# misc.net
KiCad netlist of a schematic drawn in Altium Designer
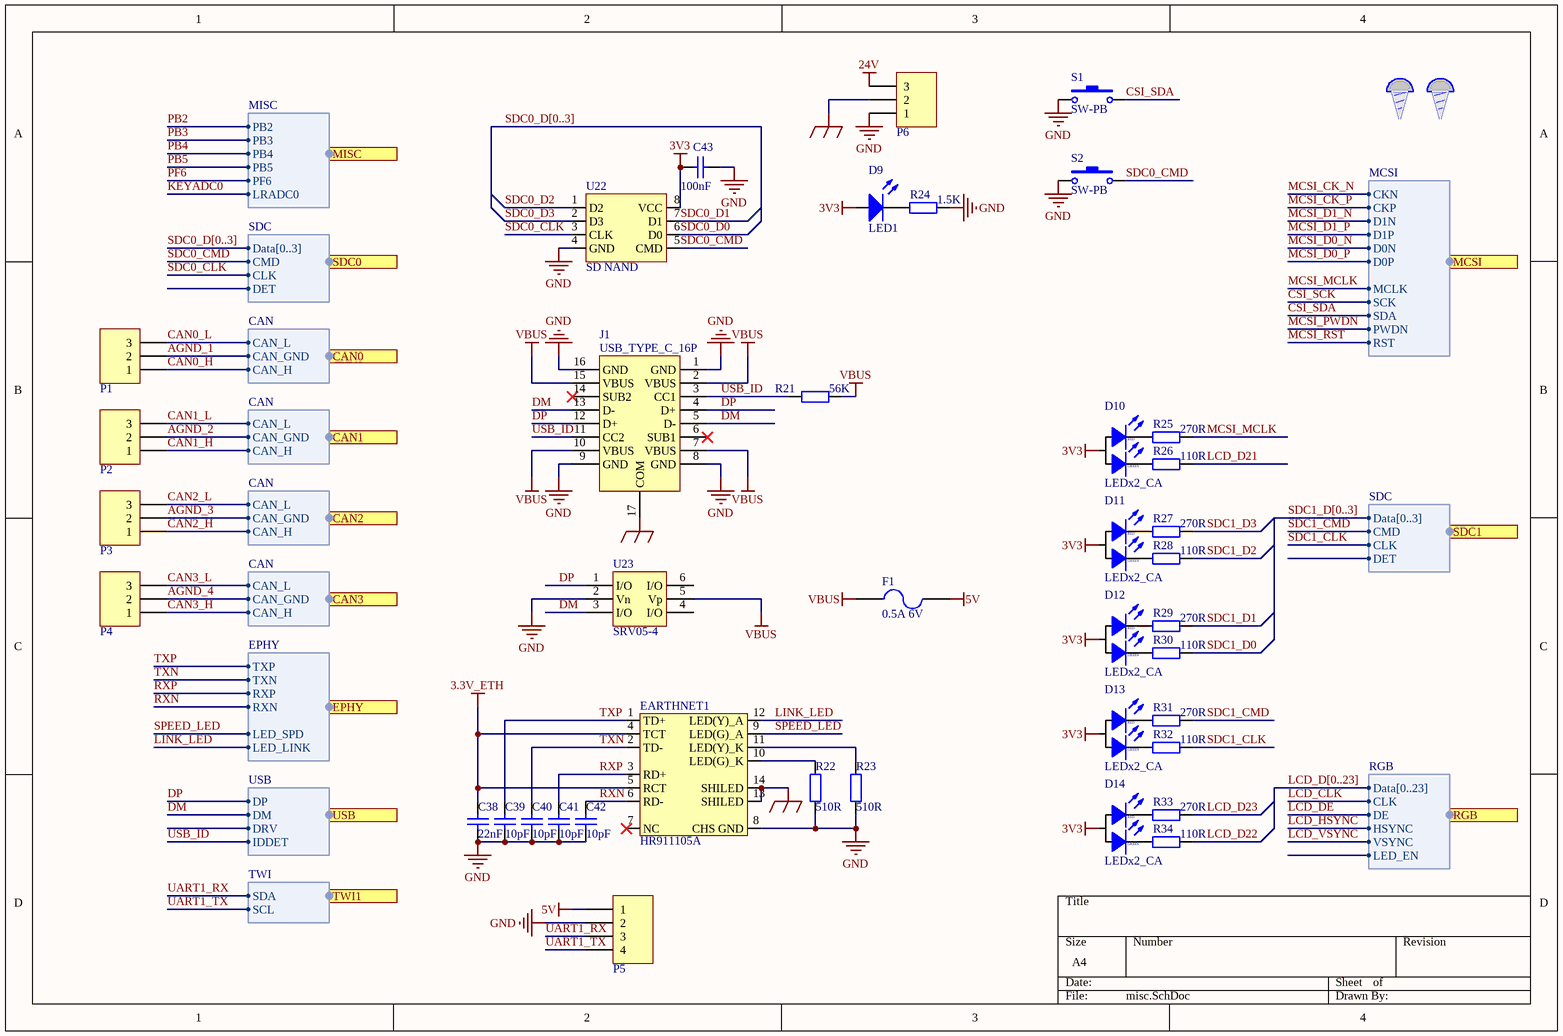
[diagram p0: misc.SchDoc]

(export (version "E")
  (design (tool "Eeschema 10.0.6"))
  (components
    (comp (ref "C38")
      (value "22nF")
      (footprint "CAPC1608L")
      (description "Capacitor")
      (fields (field (name "PUBLISHER") "Altium Limited"))
      (libsource (lib "Peace的集成库") (part "Cap1"))
    )
    (comp (ref "C39")
      (value "10pF")
      (footprint "CAPC1608L")
      (description "Capacitor")
      (fields (field (name "PUBLISHER") "Altium Limited"))
      (libsource (lib "Peace的集成库") (part "Cap1"))
    )
    (comp (ref "C40")
      (value "10pF")
      (footprint "CAPC1608L")
      (description "Capacitor")
      (fields (field (name "PUBLISHER") "Altium Limited"))
      (libsource (lib "Peace的集成库") (part "Cap1"))
    )
    (comp (ref "C41")
      (value "10pF")
      (footprint "CAPC1608L")
      (description "Capacitor")
      (fields (field (name "PUBLISHER") "Altium Limited"))
      (libsource (lib "Peace的集成库") (part "Cap1"))
    )
    (comp (ref "C42")
      (value "10pF")
      (footprint "CAPC1608L")
      (description "Capacitor")
      (fields (field (name "PUBLISHER") "Altium Limited"))
      (libsource (lib "Peace的集成库") (part "Cap1"))
    )
    (comp (ref "C43")
      (value "100nF")
      (footprint "CAPC1608L")
      (description "Capacitor")
      (fields (field (name "PUBLISHER") "Altium Limited"))
      (libsource (lib "Peace的集成库") (part "Cap1"))
    )
    (comp (ref "D9")
      (value "LED1")
      (footprint "LED_3")
      (description "Typical RED GaAs LED")
      (fields (field (name "PUBLISHER") "Altium Limited"))
      (libsource (lib "Peace的集成库") (part "LED1"))
    )
    (comp (ref "D10")
      (value "LEDx2_CA")
      (footprint "LED_3x2")
      (description "共阳红绿双色二极管")
      (fields (field (name "PUBLISHER") "Altium Limited"))
      (libsource (lib "Peace的集成库") (part "LEDx2_CA"))
    )
    (comp (ref "D11")
      (value "LEDx2_CA")
      (footprint "LED_3x2")
      (description "共阳红绿双色二极管")
      (fields (field (name "PUBLISHER") "Altium Limited"))
      (libsource (lib "Peace的集成库") (part "LEDx2_CA"))
    )
    (comp (ref "D12")
      (value "LEDx2_CA")
      (footprint "LED_3x2")
      (description "共阳红绿双色二极管")
      (fields (field (name "PUBLISHER") "Altium Limited"))
      (libsource (lib "Peace的集成库") (part "LEDx2_CA"))
    )
    (comp (ref "D13")
      (value "LEDx2_CA")
      (footprint "LED_3x2")
      (description "共阳红绿双色二极管")
      (fields (field (name "PUBLISHER") "Altium Limited"))
      (libsource (lib "Peace的集成库") (part "LEDx2_CA"))
    )
    (comp (ref "D14")
      (value "LEDx2_CA")
      (footprint "LED_3x2")
      (description "共阳红绿双色二极管")
      (fields (field (name "PUBLISHER") "Altium Limited"))
      (libsource (lib "Peace的集成库") (part "LEDx2_CA"))
    )
    (comp (ref "EARTHNET1")
      (value "HR911105A")
      (footprint "HR911105A")
      (libsource (lib "原理图库") (part "HR911105A"))
    )
    (comp (ref "F1")
      (value "0.5A 6V")
      (footprint "FUSE2012L")
      (description "Fuse")
      (fields (field (name "PUBLISHER") "Altium Limited"))
      (libsource (lib "Peace的集成库") (part "Fuse 2"))
    )
    (comp (ref "J1")
      (value "USB_TYPE_C_16P")
      (footprint "USB_TYPEC_16P")
      (libsource (lib "Peace的集成库") (part "USB_TYPE_C_16P"))
    )
    (comp (ref "M1") (value "M") (footprint "M3") (libsource (lib "Peace的集成库") (part "M")))
    (comp (ref "M2") (value "M") (footprint "M3") (libsource (lib "Peace的集成库") (part "M")))
    (comp (ref "P1")
      (value "Header 3")
      (footprint "KF2EDGR-5.08-3P_S")
      (description "Header, 3-Pin")
      (fields (field (name "PUBLISHER") "Altium Limited"))
      (libsource (lib "Peace的集成库") (part "Header 3"))
    )
    (comp (ref "P2")
      (value "Header 3")
      (footprint "KF2EDGR-5.08-3P_S")
      (description "Header, 3-Pin")
      (fields (field (name "PUBLISHER") "Altium Limited"))
      (libsource (lib "Peace的集成库") (part "Header 3"))
    )
    (comp (ref "P3")
      (value "Header 3")
      (footprint "KF2EDGR-5.08-3P_S")
      (description "Header, 3-Pin")
      (fields (field (name "PUBLISHER") "Altium Limited"))
      (libsource (lib "Peace的集成库") (part "Header 3"))
    )
    (comp (ref "P4")
      (value "Header 3")
      (footprint "KF2EDGR-5.08-3P_S")
      (description "Header, 3-Pin")
      (fields (field (name "PUBLISHER") "Altium Limited"))
      (libsource (lib "Peace的集成库") (part "Header 3"))
    )
    (comp (ref "P5")
      (value "Header 4")
      (footprint "HDR1X4")
      (description "Header, 4-Pin")
      (fields (field (name "PUBLISHER") "Altium Limited"))
      (libsource (lib "Peace的集成库") (part "Header 4"))
    )
    (comp (ref "P6")
      (value "Header 3")
      (footprint "KF2EDGR-5.08-3P_S")
      (description "Header, 3-Pin")
      (fields (field (name "PUBLISHER") "Altium Limited"))
      (libsource (lib "") (part "Header 3_1"))
    )
    (comp (ref "R21")
      (value "56K")
      (footprint "RESC1005L")
      (description "Resistor")
      (fields (field (name "PUBLISHER") "Altium Limited"))
      (libsource (lib "Peace的集成库") (part "Res1"))
    )
    (comp (ref "R22")
      (value "510R")
      (footprint "RESC1608L")
      (description "Resistor")
      (fields (field (name "PUBLISHER") "Altium Limited"))
      (libsource (lib "") (part "Res1_1"))
    )
    (comp (ref "R23")
      (value "510R")
      (footprint "RESC1608L")
      (description "Resistor")
      (fields (field (name "PUBLISHER") "Altium Limited"))
      (libsource (lib "") (part "Res1_1"))
    )
    (comp (ref "R24")
      (value "1.5K")
      (footprint "RESC1608L")
      (description "Resistor")
      (fields (field (name "PUBLISHER") "Altium Limited"))
      (libsource (lib "Peace的集成库") (part "Res1"))
    )
    (comp (ref "R25")
      (value "270R")
      (footprint "RESC1608L")
      (description "Resistor")
      (fields (field (name "PUBLISHER") "Altium Limited"))
      (libsource (lib "Peace的集成库") (part "Res1"))
    )
    (comp (ref "R26")
      (value "110R")
      (footprint "RESC1608L")
      (description "Resistor")
      (fields (field (name "PUBLISHER") "Altium Limited"))
      (libsource (lib "Peace的集成库") (part "Res1"))
    )
    (comp (ref "R27")
      (value "270R")
      (footprint "RESC1608L")
      (description "Resistor")
      (fields (field (name "PUBLISHER") "Altium Limited"))
      (libsource (lib "Peace的集成库") (part "Res1"))
    )
    (comp (ref "R28")
      (value "110R")
      (footprint "RESC1608L")
      (description "Resistor")
      (fields (field (name "PUBLISHER") "Altium Limited"))
      (libsource (lib "Peace的集成库") (part "Res1"))
    )
    (comp (ref "R29")
      (value "270R")
      (footprint "RESC1608L")
      (description "Resistor")
      (fields (field (name "PUBLISHER") "Altium Limited"))
      (libsource (lib "Peace的集成库") (part "Res1"))
    )
    (comp (ref "R30")
      (value "110R")
      (footprint "RESC1608L")
      (description "Resistor")
      (fields (field (name "PUBLISHER") "Altium Limited"))
      (libsource (lib "Peace的集成库") (part "Res1"))
    )
    (comp (ref "R31")
      (value "270R")
      (footprint "RESC1608L")
      (description "Resistor")
      (fields (field (name "PUBLISHER") "Altium Limited"))
      (libsource (lib "Peace的集成库") (part "Res1"))
    )
    (comp (ref "R32")
      (value "110R")
      (footprint "RESC1608L")
      (description "Resistor")
      (fields (field (name "PUBLISHER") "Altium Limited"))
      (libsource (lib "Peace的集成库") (part "Res1"))
    )
    (comp (ref "R33")
      (value "270R")
      (footprint "RESC1608L")
      (description "Resistor")
      (fields (field (name "PUBLISHER") "Altium Limited"))
      (libsource (lib "Peace的集成库") (part "Res1"))
    )
    (comp (ref "R34")
      (value "110R")
      (footprint "RESC1608L")
      (description "Resistor")
      (fields (field (name "PUBLISHER") "Altium Limited"))
      (libsource (lib "Peace的集成库") (part "Res1"))
    )
    (comp (ref "S1")
      (value "SW-PB")
      (footprint "SW_4.5x3.8")
      (description "Switch")
      (fields (field (name "PUBLISHER") "Altium Limited"))
      (libsource (lib "Peace的集成库") (part "SW-PB"))
    )
    (comp (ref "S2")
      (value "SW-PB")
      (footprint "SW-3x6")
      (description "Switch")
      (fields (field (name "PUBLISHER") "Altium Limited"))
      (libsource (lib "Peace的集成库") (part "SW-PB"))
    )
    (comp (ref "U22")
      (value "SD NAND")
      (footprint "QFN8_L")
      (description "贴片式SD卡")
      (libsource (lib "Peace的集成库") (part "SD NAND"))
    )
    (comp (ref "U23")
      (value "SRV05-4")
      (footprint "SOT23-6_L")
      (libsource (lib "Peace的集成库") (part "NUP4201"))
    )
  )
  (nets
    (net (code "10") (name "/AGND_1") (class "Default")
      (node (ref "P1") (pin "2") (pinfunction "2_2") (pintype "passive"))
    )
    (net (code "11") (name "/AGND_2") (class "Default")
      (node (ref "P2") (pin "2") (pinfunction "2_2") (pintype "passive"))
    )
    (net (code "12") (name "/AGND_3") (class "Default")
      (node (ref "P3") (pin "2") (pinfunction "2_2") (pintype "passive"))
    )
    (net (code "13") (name "/AGND_4") (class "Default")
      (node (ref "P4") (pin "2") (pinfunction "2_2") (pintype "passive"))
    )
    (net (code "14") (name "/CAN0_H") (class "Default")
      (node (ref "P1") (pin "1") (pinfunction "1_1") (pintype "passive"))
    )
    (net (code "15") (name "/CAN0_L") (class "Default")
      (node (ref "P1") (pin "3") (pinfunction "3_3") (pintype "passive"))
    )
    (net (code "16") (name "/CAN1_H") (class "Default")
      (node (ref "P2") (pin "1") (pinfunction "1_1") (pintype "passive"))
    )
    (net (code "17") (name "/CAN1_L") (class "Default")
      (node (ref "P2") (pin "3") (pinfunction "3_3") (pintype "passive"))
    )
    (net (code "18") (name "/CAN2_H") (class "Default")
      (node (ref "P3") (pin "1") (pinfunction "1_1") (pintype "passive"))
    )
    (net (code "19") (name "/CAN2_L") (class "Default")
      (node (ref "P3") (pin "3") (pinfunction "3_3") (pintype "passive"))
    )
    (net (code "20") (name "/CAN3_H") (class "Default")
      (node (ref "P4") (pin "1") (pinfunction "1_1") (pintype "passive"))
    )
    (net (code "21") (name "/CAN3_L") (class "Default")
      (node (ref "P4") (pin "3") (pinfunction "3_3") (pintype "passive"))
    )
    (net (code "23") (name "/CSI_SDA") (class "Default")
      (node (ref "S1") (pin "2") (pinfunction "2_2") (pintype "passive"))
    )
    (net (code "24") (name "/DM") (class "Default")
      (node (ref "J1") (pin "13") (pinfunction "D-_13") (pintype "passive"))
      (node (ref "J1") (pin "5") (pinfunction "D-_5") (pintype "passive"))
      (node (ref "U23") (pin "3") (pinfunction "I/O_3") (pintype "passive"))
    )
    (net (code "25") (name "/DP") (class "Default")
      (node (ref "J1") (pin "12") (pinfunction "D+_12") (pintype "passive"))
      (node (ref "J1") (pin "4") (pinfunction "D+_4") (pintype "passive"))
      (node (ref "U23") (pin "1") (pinfunction "I/O_1") (pintype "passive"))
    )
    (net (code "28") (name "/LCD_D21") (class "Default")
      (node (ref "R26") (pin "2") (pinfunction "2_2") (pintype "passive"))
    )
    (net (code "29") (name "/LCD_D22") (class "Default")
      (node (ref "R34") (pin "2") (pinfunction "2_2") (pintype "passive"))
    )
    (net (code "30") (name "/LCD_D23") (class "Default")
      (node (ref "R33") (pin "2") (pinfunction "2_2") (pintype "passive"))
    )
    (net (code "34") (name "/LINK_LED") (class "Default")
      (node (ref "EARTHNET1") (pin "12") (pinfunction "LED(Y)_A_12") (pintype "passive"))
    )
    (net (code "41") (name "/MCSI_MCLK") (class "Default")
      (node (ref "R25") (pin "2") (pinfunction "2_2") (pintype "passive"))
    )
    (net (code "50") (name "/RXN") (class "Default")
      (node (ref "C42") (pin "2") (pinfunction "2_2") (pintype "passive"))
      (node (ref "EARTHNET1") (pin "6") (pinfunction "RD-_6") (pintype "passive"))
    )
    (net (code "51") (name "/RXP") (class "Default")
      (node (ref "C41") (pin "2") (pinfunction "2_2") (pintype "passive"))
      (node (ref "EARTHNET1") (pin "3") (pinfunction "RD+_3") (pintype "passive"))
    )
    (net (code "52") (name "/SDC0_CLK") (class "Default")
      (node (ref "U22") (pin "3") (pinfunction "CLK_3") (pintype "passive"))
    )
    (net (code "53") (name "/SDC0_CMD") (class "Default")
      (node (ref "S2") (pin "2") (pinfunction "2_2") (pintype "passive"))
      (node (ref "U22") (pin "5") (pinfunction "CMD_5") (pintype "passive"))
    )
    (net (code "54") (name "/SDC0_D0") (class "Default")
      (node (ref "U22") (pin "6") (pinfunction "D0_6") (pintype "passive"))
    )
    (net (code "55") (name "/SDC0_D1") (class "Default")
      (node (ref "U22") (pin "7") (pinfunction "D1_7") (pintype "passive"))
    )
    (net (code "56") (name "/SDC0_D2") (class "Default")
      (node (ref "U22") (pin "1") (pinfunction "D2_1") (pintype "passive"))
    )
    (net (code "57") (name "/SDC0_D3") (class "Default")
      (node (ref "U22") (pin "2") (pinfunction "D3_2") (pintype "passive"))
    )
    (net (code "60") (name "/SDC1_CLK") (class "Default")
      (node (ref "R32") (pin "2") (pinfunction "2_2") (pintype "passive"))
    )
    (net (code "61") (name "/SDC1_CMD") (class "Default")
      (node (ref "R31") (pin "2") (pinfunction "2_2") (pintype "passive"))
    )
    (net (code "62") (name "/SDC1_D0") (class "Default")
      (node (ref "R30") (pin "2") (pinfunction "2_2") (pintype "passive"))
    )
    (net (code "63") (name "/SDC1_D1") (class "Default")
      (node (ref "R29") (pin "2") (pinfunction "2_2") (pintype "passive"))
    )
    (net (code "64") (name "/SDC1_D2") (class "Default")
      (node (ref "R28") (pin "2") (pinfunction "2_2") (pintype "passive"))
    )
    (net (code "65") (name "/SDC1_D3") (class "Default")
      (node (ref "R27") (pin "2") (pinfunction "2_2") (pintype "passive"))
    )
    (net (code "67") (name "/SPEED_LED") (class "Default")
      (node (ref "EARTHNET1") (pin "9") (pinfunction "LED(G)_A_9") (pintype "passive"))
    )
    (net (code "68") (name "/TXN") (class "Default")
      (node (ref "C40") (pin "2") (pinfunction "2_2") (pintype "passive"))
      (node (ref "EARTHNET1") (pin "2") (pinfunction "TD-_2") (pintype "passive"))
    )
    (net (code "69") (name "/TXP") (class "Default")
      (node (ref "C39") (pin "2") (pinfunction "2_2") (pintype "passive"))
      (node (ref "EARTHNET1") (pin "1") (pinfunction "TD+_1") (pintype "passive"))
    )
    (net (code "70") (name "/UART1_RX") (class "Default")
      (node (ref "P5") (pin "3") (pinfunction "3_3") (pintype "passive"))
    )
    (net (code "71") (name "/UART1_TX") (class "Default")
      (node (ref "P5") (pin "4") (pinfunction "4_4") (pintype "passive"))
    )
    (net (code "72") (name "/USB_ID") (class "Default")
      (node (ref "J1") (pin "11") (pinfunction "CC2_11") (pintype "passive"))
      (node (ref "J1") (pin "3") (pinfunction "CC1_3") (pintype "passive"))
      (node (ref "R21") (pin "1") (pinfunction "1_1") (pintype "passive"))
    )
    (net (code "82") (name "3.3V_ETH") (class "Default")
      (node (ref "C38") (pin "2") (pinfunction "2_2") (pintype "passive"))
      (node (ref "EARTHNET1") (pin "4") (pinfunction "TCT_4") (pintype "passive"))
      (node (ref "EARTHNET1") (pin "5") (pinfunction "RCT_5") (pintype "passive"))
    )
    (net (code "83") (name "3V3") (class "Default")
      (node (ref "C43") (pin "1") (pinfunction "1_1") (pintype "passive"))
      (node (ref "D10") (pin "2") (pinfunction "A_2") (pintype "passive"))
      (node (ref "D11") (pin "2") (pinfunction "A_2") (pintype "passive"))
      (node (ref "D12") (pin "2") (pinfunction "A_2") (pintype "passive"))
      (node (ref "D13") (pin "2") (pinfunction "A_2") (pintype "passive"))
      (node (ref "D14") (pin "2") (pinfunction "A_2") (pintype "passive"))
      (node (ref "D9") (pin "1") (pinfunction "A_1") (pintype "passive"))
      (node (ref "U22") (pin "8") (pinfunction "VCC_8") (pintype "passive"))
    )
    (net (code "84") (name "5V") (class "Default")
      (node (ref "F1") (pin "2") (pinfunction "2_2") (pintype "passive"))
      (node (ref "P5") (pin "1") (pinfunction "1_1") (pintype "passive"))
    )
    (net (code "85") (name "24V") (class "Default")
      (node (ref "P6") (pin "3") (pinfunction "3_3") (pintype "passive"))
    )
    (net (code "86") (name "EARTH") (class "Default")
      (node (ref "EARTHNET1") (pin "13") (pinfunction "SHILED_13") (pintype "passive"))
      (node (ref "EARTHNET1") (pin "14") (pinfunction "SHILED_14") (pintype "passive"))
      (node (ref "J1") (pin "17") (pinfunction "COM_17") (pintype "passive"))
      (node (ref "P6") (pin "2") (pinfunction "2_2") (pintype "passive"))
    )
    (net (code "87") (name "GND") (class "Default")
      (node (ref "C38") (pin "1") (pinfunction "1_1") (pintype "passive"))
      (node (ref "C39") (pin "1") (pinfunction "1_1") (pintype "passive"))
      (node (ref "C40") (pin "1") (pinfunction "1_1") (pintype "passive"))
      (node (ref "C41") (pin "1") (pinfunction "1_1") (pintype "passive"))
      (node (ref "C42") (pin "1") (pinfunction "1_1") (pintype "passive"))
      (node (ref "C43") (pin "2") (pinfunction "2_2") (pintype "passive"))
      (node (ref "EARTHNET1") (pin "8") (pinfunction "CHS_GND_8") (pintype "passive"))
      (node (ref "J1") (pin "1") (pinfunction "GND_1") (pintype "passive"))
      (node (ref "J1") (pin "16") (pinfunction "GND_16") (pintype "passive"))
      (node (ref "J1") (pin "8") (pinfunction "GND_8") (pintype "passive"))
      (node (ref "J1") (pin "9") (pinfunction "GND_9") (pintype "passive"))
      (node (ref "P5") (pin "2") (pinfunction "2_2") (pintype "passive"))
      (node (ref "P6") (pin "1") (pinfunction "1_1") (pintype "passive"))
      (node (ref "R22") (pin "1") (pinfunction "1_1") (pintype "passive"))
      (node (ref "R23") (pin "1") (pinfunction "1_1") (pintype "passive"))
      (node (ref "R24") (pin "2") (pinfunction "2_2") (pintype "passive"))
      (node (ref "S1") (pin "1") (pinfunction "1_1") (pintype "passive"))
      (node (ref "S2") (pin "1") (pinfunction "1_1") (pintype "passive"))
      (node (ref "U22") (pin "4") (pinfunction "GND_4") (pintype "passive"))
      (node (ref "U23") (pin "2") (pinfunction "Vn_2") (pintype "passive"))
    )
    (net (code "88") (name "Net-(D9-K)") (class "Default")
      (node (ref "D9") (pin "2") (pinfunction "K_2") (pintype "passive"))
      (node (ref "R24") (pin "1") (pinfunction "1_1") (pintype "passive"))
    )
    (net (code "89") (name "Net-(D10-K-Pad1)") (class "Default")
      (node (ref "D10") (pin "1") (pinfunction "K_1") (pintype "passive"))
      (node (ref "R26") (pin "1") (pinfunction "1_1") (pintype "passive"))
    )
    (net (code "90") (name "Net-(D10-K-Pad3)") (class "Default")
      (node (ref "D10") (pin "3") (pinfunction "K_3") (pintype "passive"))
      (node (ref "R25") (pin "1") (pinfunction "1_1") (pintype "passive"))
    )
    (net (code "91") (name "Net-(D11-K-Pad1)") (class "Default")
      (node (ref "D11") (pin "1") (pinfunction "K_1") (pintype "passive"))
      (node (ref "R28") (pin "1") (pinfunction "1_1") (pintype "passive"))
    )
    (net (code "92") (name "Net-(D11-K-Pad3)") (class "Default")
      (node (ref "D11") (pin "3") (pinfunction "K_3") (pintype "passive"))
      (node (ref "R27") (pin "1") (pinfunction "1_1") (pintype "passive"))
    )
    (net (code "93") (name "Net-(D12-K-Pad1)") (class "Default")
      (node (ref "D12") (pin "1") (pinfunction "K_1") (pintype "passive"))
      (node (ref "R30") (pin "1") (pinfunction "1_1") (pintype "passive"))
    )
    (net (code "94") (name "Net-(D12-K-Pad3)") (class "Default")
      (node (ref "D12") (pin "3") (pinfunction "K_3") (pintype "passive"))
      (node (ref "R29") (pin "1") (pinfunction "1_1") (pintype "passive"))
    )
    (net (code "95") (name "Net-(D13-K-Pad1)") (class "Default")
      (node (ref "D13") (pin "1") (pinfunction "K_1") (pintype "passive"))
      (node (ref "R32") (pin "1") (pinfunction "1_1") (pintype "passive"))
    )
    (net (code "96") (name "Net-(D13-K-Pad3)") (class "Default")
      (node (ref "D13") (pin "3") (pinfunction "K_3") (pintype "passive"))
      (node (ref "R31") (pin "1") (pinfunction "1_1") (pintype "passive"))
    )
    (net (code "97") (name "Net-(D14-K-Pad1)") (class "Default")
      (node (ref "D14") (pin "1") (pinfunction "K_1") (pintype "passive"))
      (node (ref "R34") (pin "1") (pinfunction "1_1") (pintype "passive"))
    )
    (net (code "98") (name "Net-(D14-K-Pad3)") (class "Default")
      (node (ref "D14") (pin "3") (pinfunction "K_3") (pintype "passive"))
      (node (ref "R33") (pin "1") (pinfunction "1_1") (pintype "passive"))
    )
    (net (code "99") (name "Net-(EARTHNET1-LED(G)_K)") (class "Default")
      (node (ref "EARTHNET1") (pin "10") (pinfunction "LED(G)_K_10") (pintype "passive"))
      (node (ref "R22") (pin "2") (pinfunction "2_2") (pintype "passive"))
    )
    (net (code "100") (name "Net-(EARTHNET1-LED(Y)_K)") (class "Default")
      (node (ref "EARTHNET1") (pin "11") (pinfunction "LED(Y)_K_11") (pintype "passive"))
      (node (ref "R23") (pin "2") (pinfunction "2_2") (pintype "passive"))
    )
    (net (code "101") (name "VBUS") (class "Default")
      (node (ref "F1") (pin "1") (pinfunction "1_1") (pintype "passive"))
      (node (ref "J1") (pin "10") (pinfunction "VBUS_10") (pintype "passive"))
      (node (ref "J1") (pin "15") (pinfunction "VBUS_15") (pintype "passive"))
      (node (ref "J1") (pin "2") (pinfunction "VBUS_2") (pintype "passive"))
      (node (ref "J1") (pin "7") (pinfunction "VBUS_7") (pintype "passive"))
      (node (ref "R21") (pin "2") (pinfunction "2_2") (pintype "passive"))
      (node (ref "U23") (pin "5") (pinfunction "Vp_5") (pintype "passive"))
    )
    (net (code "102") (name "unconnected-(EARTHNET1-NC-Pad7)") (class "Default")
      (node (ref "EARTHNET1") (pin "7") (pinfunction "NC_7") (pintype "passive+no_connect"))
    )
    (net (code "103") (name "unconnected-(J1-SUB1-Pad6)") (class "Default")
      (node (ref "J1") (pin "6") (pinfunction "SUB1_6") (pintype "passive+no_connect"))
    )
    (net (code "104") (name "unconnected-(J1-SUB2-Pad14)") (class "Default")
      (node (ref "J1") (pin "14") (pinfunction "SUB2_14") (pintype "passive+no_connect"))
    )
    (net (code "105") (name "unconnected-(U23-I{slash}O-Pad4)") (class "Default")
      (node (ref "U23") (pin "4") (pinfunction "I/O_4") (pintype "passive"))
    )
    (net (code "106") (name "unconnected-(U23-I{slash}O-Pad6)") (class "Default")
      (node (ref "U23") (pin "6") (pinfunction "I/O_6") (pintype "passive"))
    )
  )
)
